# schematic.net
KiCad netlist of a schematic drawn in EasyEDA
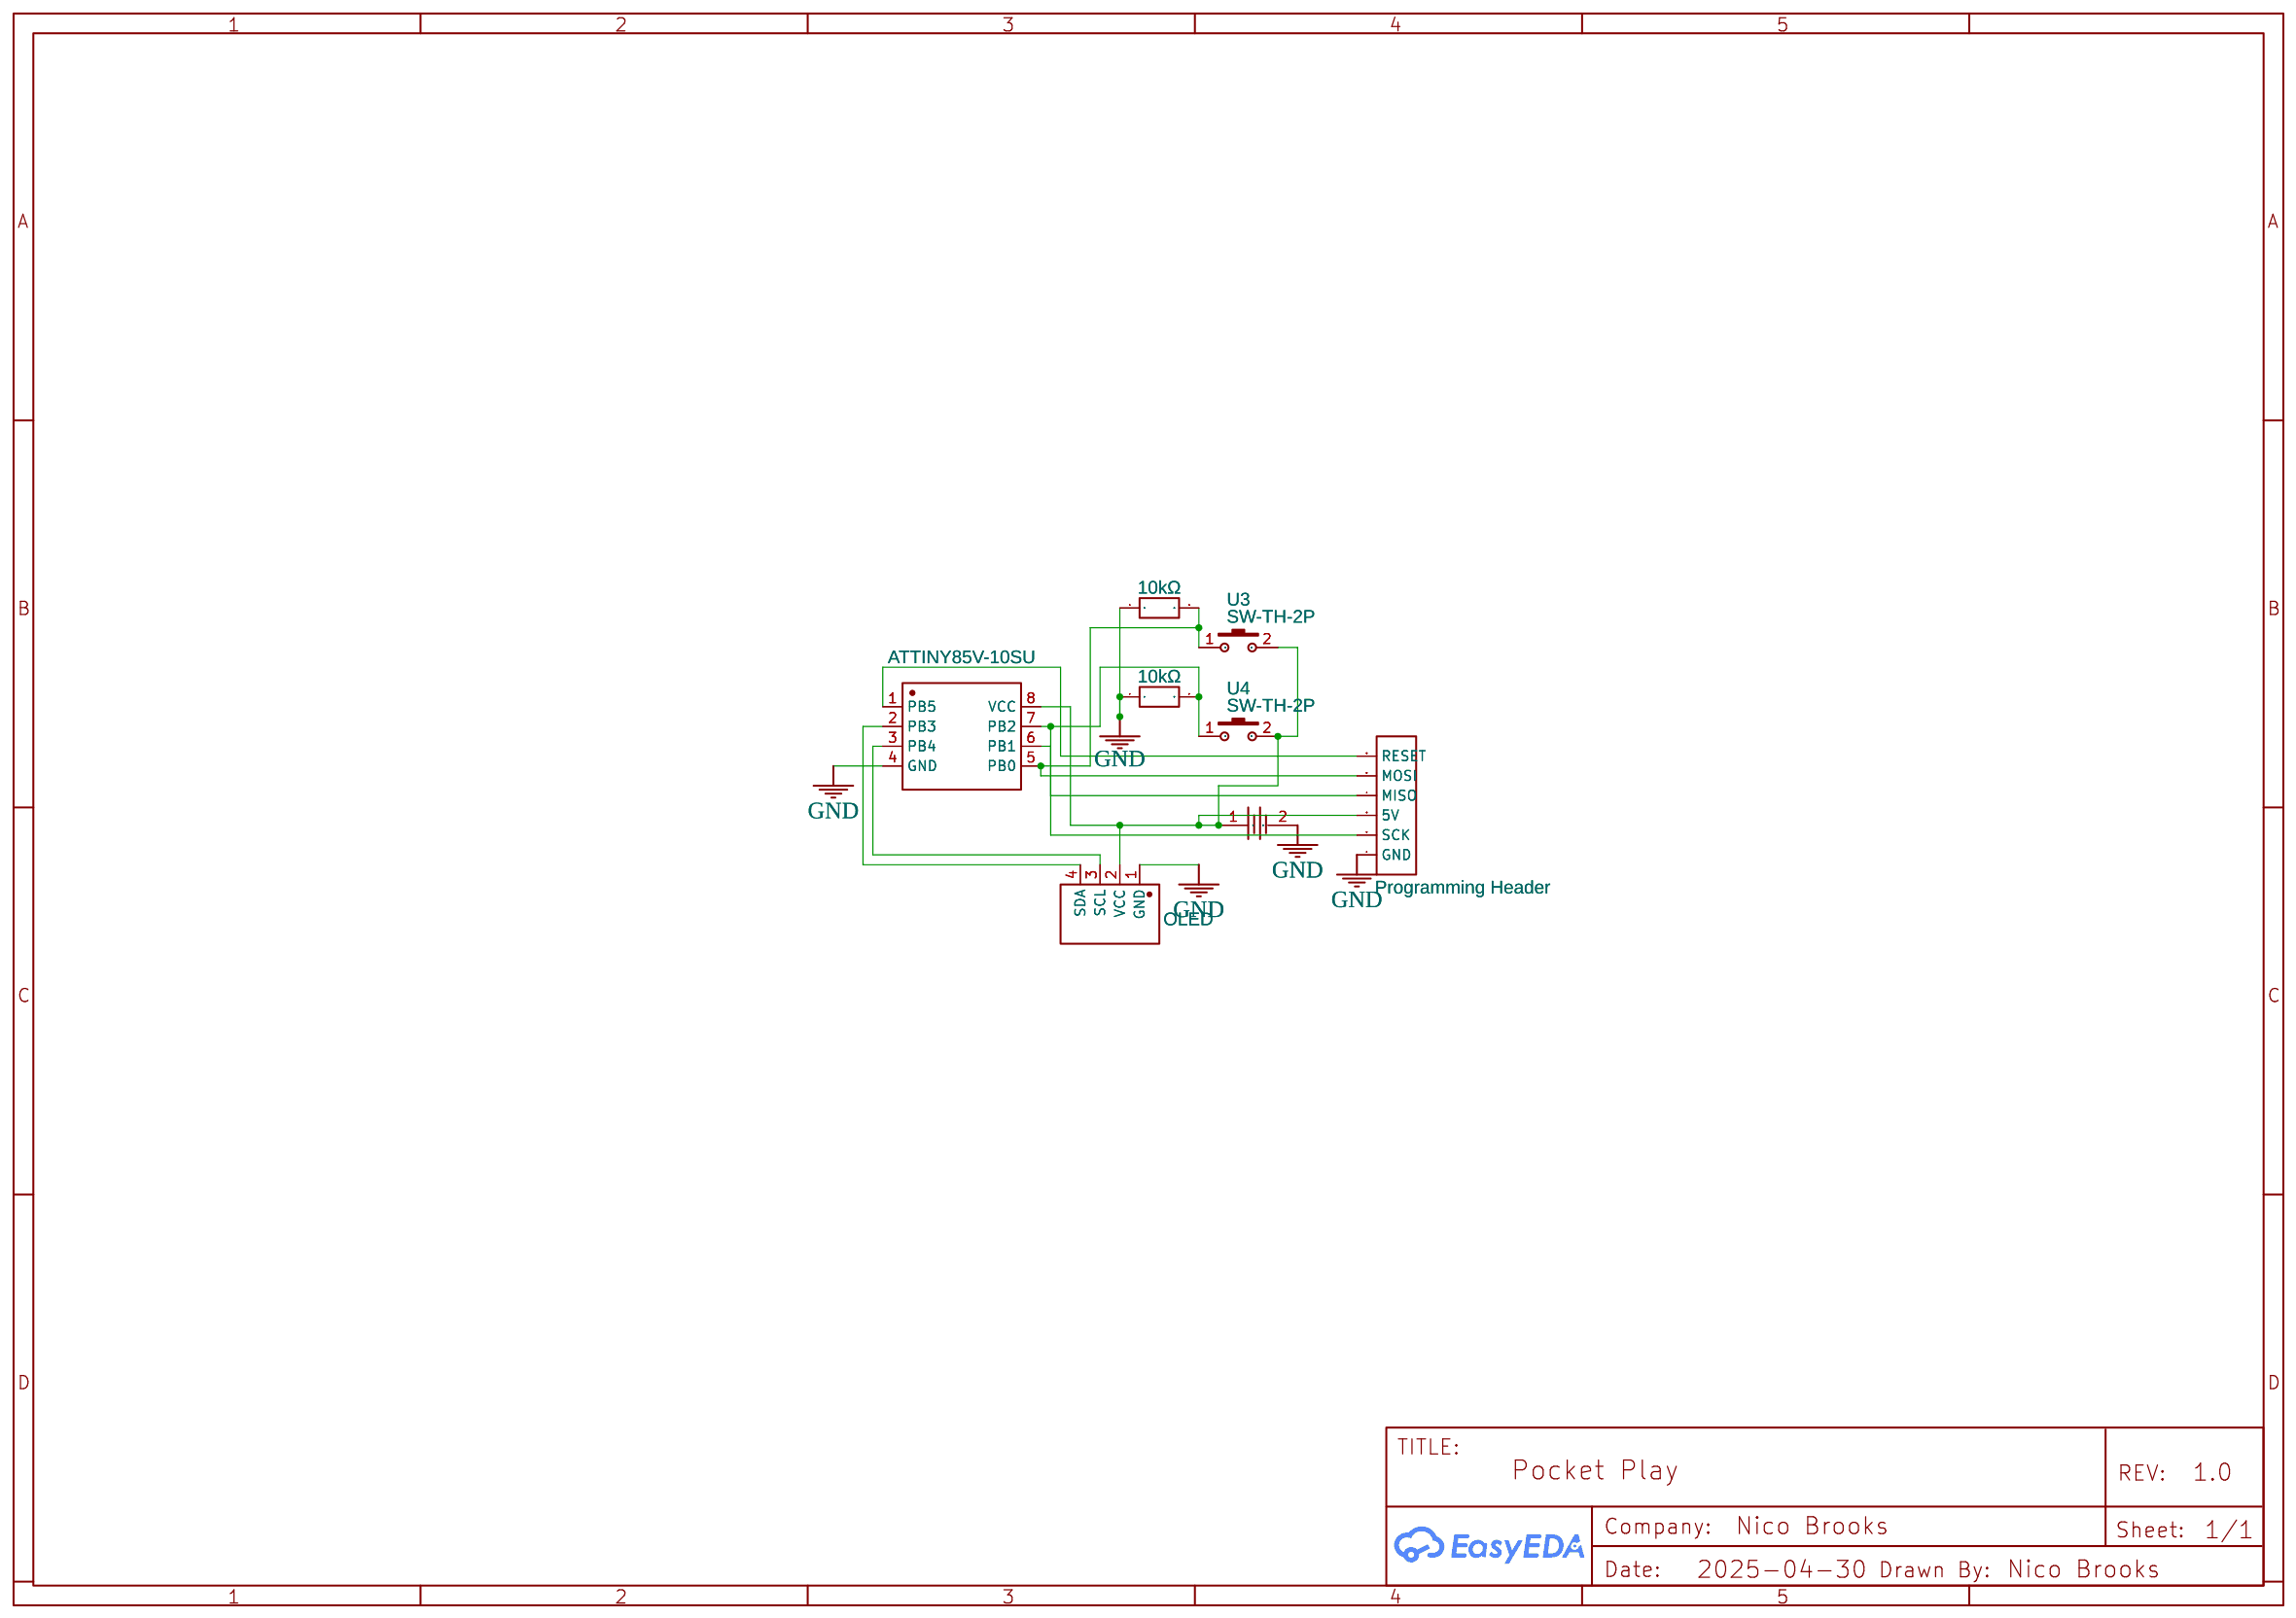
[diagram p0: schematic sheet]

(export (version "E")
  (design (tool "Eeschema 10.0.6"))
  (components
    (comp (ref "B1")
      (value "CR2032")
      (fields (field (name "Manufacturer Part") "CR2032-BS-6-1") (field (name "Manufacturer") "Q&J"))
      (libsource (lib "") (part "CR2032-BS-6-1"))
    )
    (comp (ref "J1") (value "Programming Header") (libsource (lib "") (part "HEADER_6")))
    (comp (ref "OLED1")
      (value "OLED")
      (fields (field (name "Manufacturer Part") "UN-2864KMBEG01"))
      (libsource (lib "") (part "UN-2864KMBEG01"))
    )
    (comp (ref "U1")
      (value "10kΩ")
      (fields (field (name "Manufacturer Part") "CR1/4W-10K±5%-OT26") (field (name "Manufacturer") "VO(翔胜)"))
      (libsource (lib "") (part "CR1/4W-10K±5%-OT26"))
    )
    (comp (ref "U2")
      (value "10kΩ")
      (fields (field (name "Manufacturer Part") "CR1/4W-10K±5%-OT26") (field (name "Manufacturer") "VO(翔胜)"))
      (libsource (lib "") (part "CR1/4W-10K±5%-OT26"))
    )
    (comp (ref "U3") (value "SW-TH-2P") (libsource (lib "") (part "SW-TH-2P")))
    (comp (ref "U4") (value "SW-TH-2P") (libsource (lib "") (part "SW-TH-2P")))
    (comp (ref "U6")
      (value "ATTINY85V-10SU")
      (fields (field (name "Manufacturer") "MICROCHIP(美国微芯)"))
      (libsource (lib "") (part "ATTINY85V-10SU"))
    )
  )
  (nets
    (net (code "1") (name "GND") (class "Default")
      (node (ref "B1") (pin "2") (pinfunction "2_2") (pintype "input"))
      (node (ref "J1") (pin "1") (pinfunction "GND_1") (pintype "input"))
      (node (ref "OLED1") (pin "1") (pinfunction "GND_1") (pintype "unspecified"))
      (node (ref "U1") (pin "1") (pinfunction "1_1") (pintype "unspecified"))
      (node (ref "U2") (pin "1") (pinfunction "1_1") (pintype "unspecified"))
      (node (ref "U6") (pin "4") (pinfunction "GND_4") (pintype "unspecified"))
    )
    (net (code "2") (name "Net-(J1-5V)") (class "Default")
      (node (ref "B1") (pin "1") (pinfunction "1_1") (pintype "input"))
      (node (ref "J1") (pin "3") (pinfunction "5V_3") (pintype "input"))
      (node (ref "OLED1") (pin "2") (pinfunction "VCC_2") (pintype "unspecified"))
      (node (ref "U3") (pin "2") (pinfunction "2_2") (pintype "unspecified"))
      (node (ref "U4") (pin "2") (pinfunction "2_2") (pintype "unspecified"))
      (node (ref "U6") (pin "8") (pinfunction "VCC_8") (pintype "unspecified"))
    )
    (net (code "3") (name "Net-(J1-MISO)") (class "Default")
      (node (ref "J1") (pin "4") (pinfunction "MISO_4") (pintype "input"))
      (node (ref "U6") (pin "6") (pinfunction "PB1_6") (pintype "unspecified"))
    )
    (net (code "4") (name "Net-(J1-MOSI)") (class "Default")
      (node (ref "J1") (pin "5") (pinfunction "MOSI_5") (pintype "input"))
      (node (ref "U1") (pin "2") (pinfunction "2_2") (pintype "unspecified"))
      (node (ref "U3") (pin "1") (pinfunction "1_1") (pintype "unspecified"))
      (node (ref "U6") (pin "5") (pinfunction "PB0_5") (pintype "unspecified"))
    )
    (net (code "5") (name "Net-(J1-RESET)") (class "Default")
      (node (ref "J1") (pin "6") (pinfunction "RESET_6") (pintype "input"))
      (node (ref "U6") (pin "1") (pinfunction "PB5_1") (pintype "unspecified"))
    )
    (net (code "6") (name "Net-(J1-SCK)") (class "Default")
      (node (ref "J1") (pin "2") (pinfunction "SCK_2") (pintype "input"))
      (node (ref "U2") (pin "2") (pinfunction "2_2") (pintype "unspecified"))
      (node (ref "U4") (pin "1") (pinfunction "1_1") (pintype "unspecified"))
      (node (ref "U6") (pin "7") (pinfunction "PB2_7") (pintype "unspecified"))
    )
    (net (code "7") (name "Net-(OLED1-SCL)") (class "Default")
      (node (ref "OLED1") (pin "3") (pinfunction "SCL_3") (pintype "unspecified"))
      (node (ref "U6") (pin "3") (pinfunction "PB4_3") (pintype "unspecified"))
    )
    (net (code "8") (name "Net-(OLED1-SDA)") (class "Default")
      (node (ref "OLED1") (pin "4") (pinfunction "SDA_4") (pintype "unspecified"))
      (node (ref "U6") (pin "2") (pinfunction "PB3_2") (pintype "unspecified"))
    )
  )
)
